# SmartSwitch_V1_3.net
KiCad netlist of a schematic drawn in EAGLE
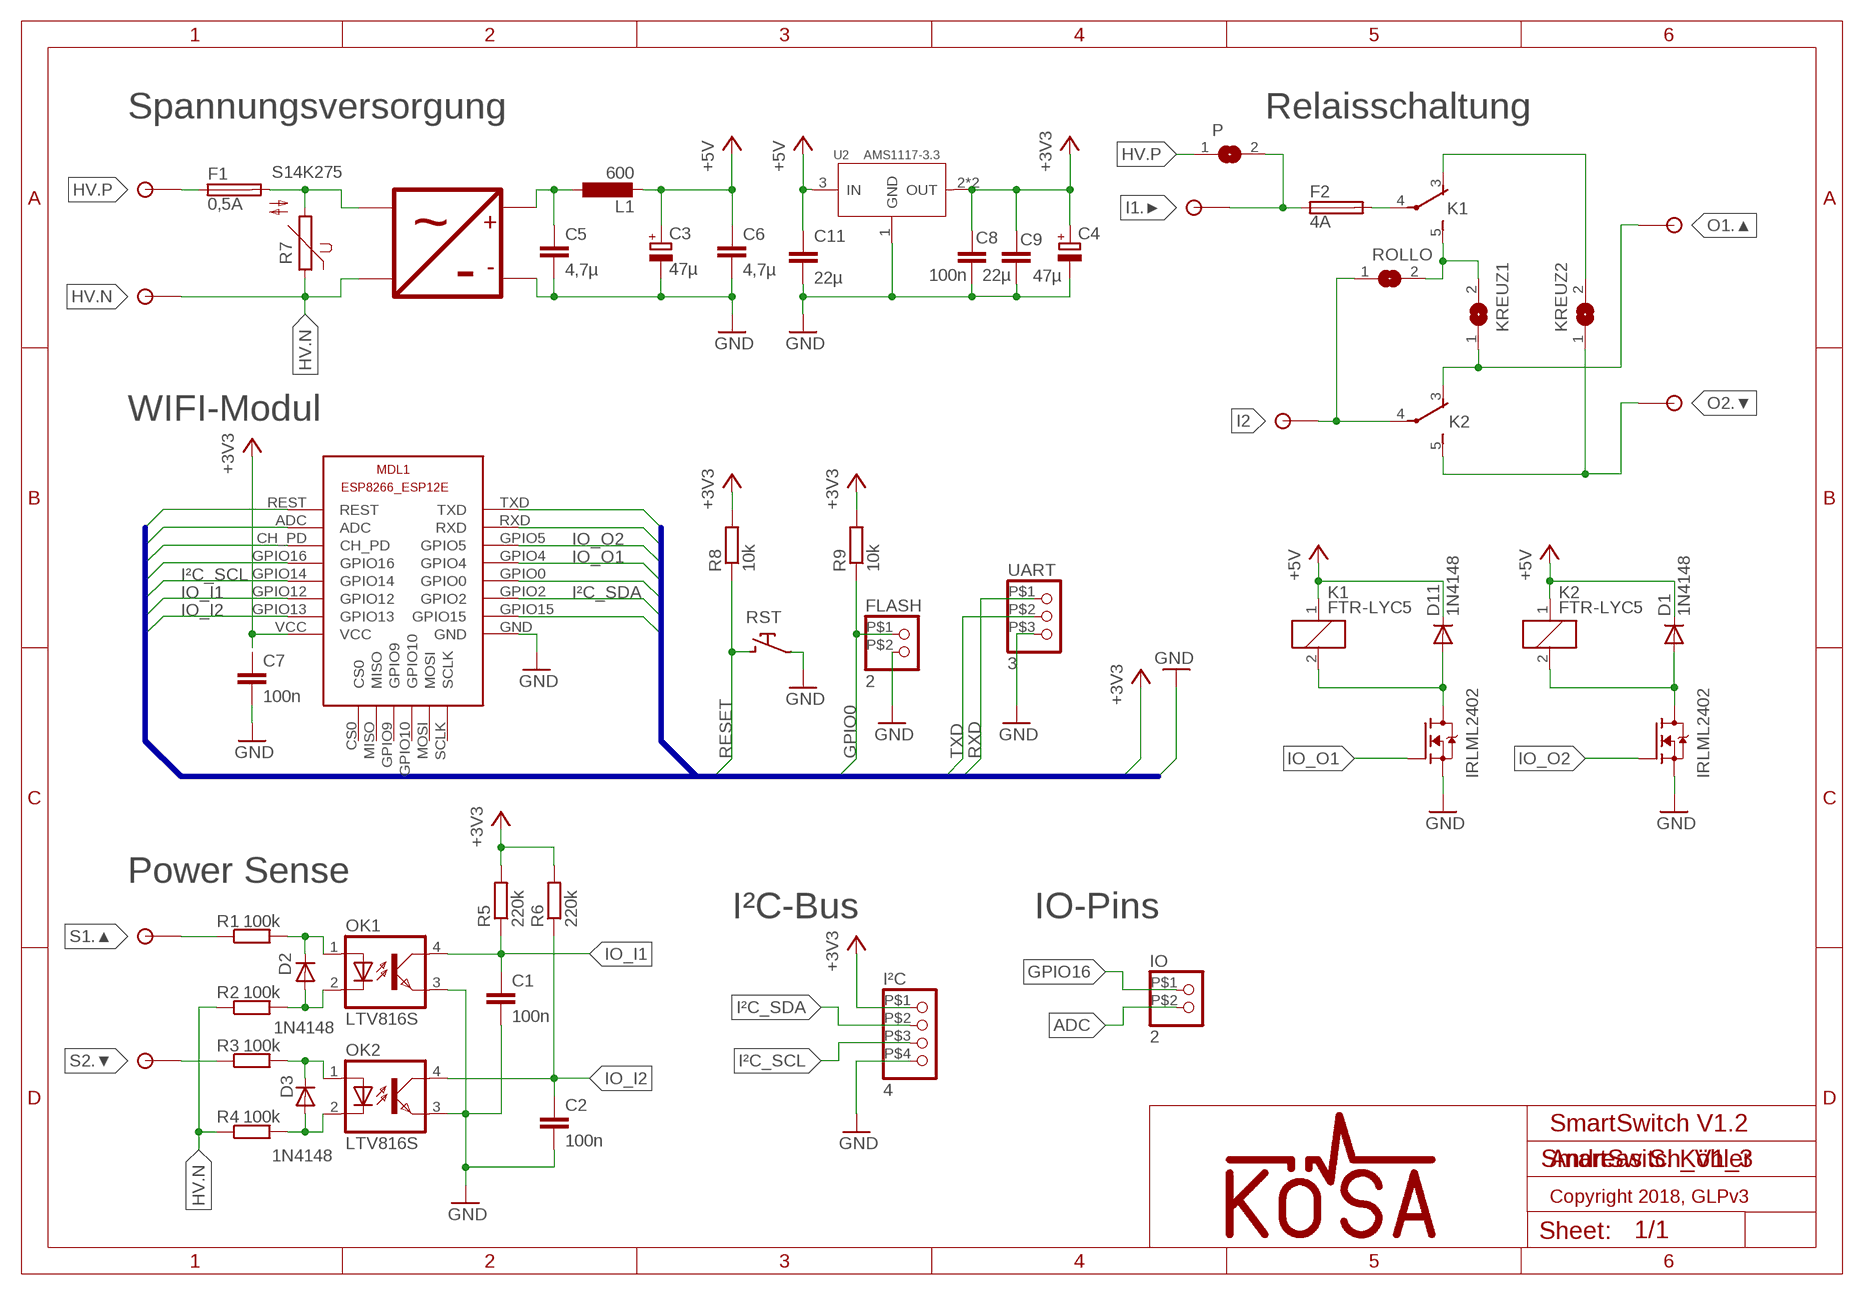
[diagram p0: schematic, sheet 1]

(export (version "E")
  (design (tool "Eeschema 10.0.6"))
  (components
    (comp (ref "C1")
      (value "100n")
      (footprint "eagle-import:C0805")
      (libsource (lib "eagle-import") (part "C-EUC0805"))
    )
    (comp (ref "C2")
      (value "100n")
      (footprint "eagle-import:C0805")
      (libsource (lib "eagle-import") (part "C-EUC0805"))
    )
    (comp (ref "C3")
      (value "47µ")
      (footprint "eagle-import:E2-5")
      (libsource (lib "eagle-import") (part "CPOL-EUE2-5"))
    )
    (comp (ref "C4")
      (value "47µ")
      (footprint "eagle-import:E2-5")
      (libsource (lib "eagle-import") (part "CPOL-EUE2-5"))
    )
    (comp (ref "C5")
      (value "4,7µ")
      (footprint "eagle-import:C0805")
      (libsource (lib "eagle-import") (part "C-EUC0805"))
    )
    (comp (ref "C6")
      (value "4,7µ")
      (footprint "eagle-import:C0805")
      (libsource (lib "eagle-import") (part "C-EUC0805"))
    )
    (comp (ref "C7")
      (value "100n")
      (footprint "eagle-import:C0805")
      (libsource (lib "eagle-import") (part "C-EUC0805"))
    )
    (comp (ref "C8")
      (value "100n")
      (footprint "eagle-import:C0805")
      (libsource (lib "eagle-import") (part "C-EUC0805"))
    )
    (comp (ref "C9")
      (value "22µ")
      (footprint "eagle-import:C0805")
      (libsource (lib "eagle-import") (part "C-EUC0805"))
    )
    (comp (ref "C11")
      (value "22µ")
      (footprint "eagle-import:C0805")
      (libsource (lib "eagle-import") (part "C-EUC0805"))
    )
    (comp (ref "D1")
      (value "1N4148")
      (footprint "eagle-import:SOD323-W")
      (libsource (lib "eagle-import") (part "DIODE-SOD323-W"))
    )
    (comp (ref "D2")
      (value "1N4148")
      (footprint "eagle-import:SOD323-W")
      (libsource (lib "eagle-import") (part "DIODE-SOD323-W"))
    )
    (comp (ref "D3")
      (value "1N4148")
      (footprint "eagle-import:SOD323-W")
      (libsource (lib "eagle-import") (part "DIODE-SOD323-W"))
    )
    (comp (ref "D11")
      (value "1N4148")
      (footprint "eagle-import:SOD323-W")
      (libsource (lib "eagle-import") (part "DIODE-SOD323-W"))
    )
    (comp (ref "F1")
      (value "0,5A")
      (footprint "eagle-import:SMD_FUSE_HOLDER")
      (libsource (lib "eagle-import") (part "SMD_FUSE_HOLDER"))
    )
    (comp (ref "F2")
      (value "4A")
      (footprint "eagle-import:SMD_FUSE_HOLDER")
      (libsource (lib "eagle-import") (part "SMD_FUSE_HOLDER"))
    )
    (comp (ref "FLASH")
      (value "2")
      (footprint "eagle-import:1X02_SMALL")
      (libsource (lib "eagle-import") (part "PINHD-1X2SMALL"))
    )
    (comp (ref "IO")
      (value "2")
      (footprint "eagle-import:1X02_SMALL")
      (libsource (lib "eagle-import") (part "PINHD-1X2SMALL"))
    )
    (comp (ref "I²C")
      (value "4")
      (footprint "eagle-import:1X04_SMALL")
      (libsource (lib "eagle-import") (part "PINHD-1X4SMALL"))
    )
    (comp (ref "K1")
      (value "FTR-LYC5")
      (footprint "eagle-import:FTR-LYC")
      (libsource (lib "eagle-import") (part "FTR-LYC5"))
    )
    (comp (ref "K2")
      (value "FTR-LYC5")
      (footprint "eagle-import:FTR-LYC")
      (libsource (lib "eagle-import") (part "FTR-LYC5"))
    )
    (comp (ref "KREUZ1")
      (value "SJW")
      (footprint "eagle-import:SJW")
      (libsource (lib "eagle-import") (part "SJW"))
    )
    (comp (ref "KREUZ2")
      (value "SJW")
      (footprint "eagle-import:SJW")
      (libsource (lib "eagle-import") (part "SJW"))
    )
    (comp (ref "L1")
      (value "600")
      (footprint "eagle-import:L3225P")
      (libsource (lib "eagle-import") (part "L-EUL3225P"))
    )
    (comp (ref "MDL1")
      (value "1")
      (footprint "eagle-import:ESP8266-ESP12E")
      (libsource (lib "eagle-import") (part "ESP8266-12EESP8266-ESP12E"))
    )
    (comp (ref "OK1")
      (value "LTV816S")
      (footprint "eagle-import:SMD4")
      (libsource (lib "eagle-import") (part "LTV816S"))
    )
    (comp (ref "OK2")
      (value "LTV816S")
      (footprint "eagle-import:SMD4")
      (libsource (lib "eagle-import") (part "LTV816S"))
    )
    (comp (ref "P")
      (value "SJW")
      (footprint "eagle-import:SJW")
      (libsource (lib "eagle-import") (part "SJW"))
    )
    (comp (ref "R1")
      (value "100k")
      (footprint "eagle-import:R1206")
      (libsource (lib "eagle-import") (part "R-EU_R1206"))
    )
    (comp (ref "R2")
      (value "100k")
      (footprint "eagle-import:R1206")
      (libsource (lib "eagle-import") (part "R-EU_R1206"))
    )
    (comp (ref "R3")
      (value "100k")
      (footprint "eagle-import:R1206")
      (libsource (lib "eagle-import") (part "R-EU_R1206"))
    )
    (comp (ref "R4")
      (value "100k")
      (footprint "eagle-import:R1206")
      (libsource (lib "eagle-import") (part "R-EU_R1206"))
    )
    (comp (ref "R5")
      (value "220k")
      (footprint "eagle-import:R1206")
      (libsource (lib "eagle-import") (part "R-EU_R1206"))
    )
    (comp (ref "R6")
      (value "220k")
      (footprint "eagle-import:R1206")
      (libsource (lib "eagle-import") (part "R-EU_R1206"))
    )
    (comp (ref "R7")
      (value "S14K275")
      (footprint "eagle-import:S14K275_")
      (libsource (lib "eagle-import") (part "S14K275GESPIEGELT"))
    )
    (comp (ref "R8")
      (value "10k")
      (footprint "eagle-import:R1206")
      (libsource (lib "eagle-import") (part "R-EU_R1206"))
    )
    (comp (ref "R9")
      (value "10k")
      (footprint "eagle-import:R1206")
      (libsource (lib "eagle-import") (part "R-EU_R1206"))
    )
    (comp (ref "ROLLO")
      (value "SJW")
      (footprint "eagle-import:SJW")
      (libsource (lib "eagle-import") (part "SJW"))
    )
    (comp (ref "RST")
      (value "SMD-TASTER_REICHELT_KMR_231_G_LFS")
      (footprint "eagle-import:SMD-TASTER_REICHELT_KMR_231_G_LFS")
      (libsource (lib "eagle-import") (part "SMD-TASTER_REICHELT_KMR_231_G_LFS"))
    )
    (comp (ref "U$1")
      (value "HLK-PM01")
      (footprint "eagle-import:HLK-PM01")
      (libsource (lib "eagle-import") (part "HLK-PM01"))
    )
    (comp (ref "U$2")
      (value "RND_205-00276")
      (footprint "eagle-import:RND205-00276")
      (libsource (lib "eagle-import") (part "RND_205-00276"))
    )
    (comp (ref "U$3")
      (value "RND_205-00276")
      (footprint "eagle-import:RND205-00276")
      (libsource (lib "eagle-import") (part "RND_205-00276"))
    )
    (comp (ref "U$4")
      (value "RND_205-00276")
      (footprint "eagle-import:RND205-00276")
      (libsource (lib "eagle-import") (part "RND_205-00276"))
    )
    (comp (ref "U$5")
      (value "RND_205-00276")
      (footprint "eagle-import:RND205-00276")
      (libsource (lib "eagle-import") (part "RND_205-00276"))
    )
    (comp (ref "U$7")
      (value "IRLML2402")
      (footprint "eagle-import:SOT23")
      (libsource (lib "eagle-import") (part "IRLML2502"))
    )
    (comp (ref "U$8")
      (value "IRLML2402")
      (footprint "eagle-import:SOT23")
      (libsource (lib "eagle-import") (part "IRLML2502"))
    )
    (comp (ref "U2")
      (value "AMS1117-3.3")
      (footprint "eagle-import:SOT-223")
      (fields (field (name "MPN") "CJT1117-3.3"))
      (libsource (lib "eagle-import") (part "PMIC-CJT1117-3.3(SOT223)"))
    )
    (comp (ref "UART")
      (value "3")
      (footprint "eagle-import:1X03_SMALL")
      (libsource (lib "eagle-import") (part "PINHD-1X3SMALL"))
    )
  )
  (nets
    (net (code "1") (name "+3V3") (class "Default")
      (node (ref "C4") (pin "+") (pinfunction "+_+") (pintype "passive"))
      (node (ref "C7") (pin "1") (pinfunction "1_1") (pintype "passive"))
      (node (ref "C8") (pin "1") (pinfunction "1_1") (pintype "passive"))
      (node (ref "C9") (pin "1") (pinfunction "1_1") (pintype "passive"))
      (node (ref "I²C") (pin "P$1") (pinfunction "1_P$1") (pintype "passive"))
      (node (ref "MDL1") (pin "CH_PD") (pinfunction "CH_PD_CH_PD") (pintype "bidirectional"))
      (node (ref "MDL1") (pin "VCC") (pinfunction "VCC_VCC") (pintype "bidirectional"))
      (node (ref "R5") (pin "2") (pinfunction "2_2") (pintype "passive"))
      (node (ref "R6") (pin "2") (pinfunction "2_2") (pintype "passive"))
      (node (ref "R8") (pin "2") (pinfunction "2_2") (pintype "passive"))
      (node (ref "R9") (pin "2") (pinfunction "2_2") (pintype "passive"))
      (node (ref "U2") (pin "2") (pinfunction "OUT_2") (pintype "bidirectional"))
      (node (ref "U2") (pin "TER") (pinfunction "OUT_TER") (pintype "bidirectional"))
    )
    (net (code "2") (name "+5V") (class "Default")
      (node (ref "C11") (pin "1") (pinfunction "1_1") (pintype "passive"))
      (node (ref "C3") (pin "+") (pinfunction "+_+") (pintype "passive"))
      (node (ref "C6") (pin "1") (pinfunction "1_1") (pintype "passive"))
      (node (ref "D1") (pin "C") (pinfunction "C_C") (pintype "passive"))
      (node (ref "D11") (pin "C") (pinfunction "C_C") (pintype "passive"))
      (node (ref "K1") (pin "1") (pinfunction "1_1") (pintype "passive"))
      (node (ref "K2") (pin "1") (pinfunction "1_1") (pintype "passive"))
      (node (ref "L1") (pin "2") (pinfunction "2_2") (pintype "passive"))
      (node (ref "U2") (pin "3") (pinfunction "IN_3") (pintype "bidirectional"))
    )
    (net (code "3") (name "/GPIO0") (class "Default")
      (node (ref "FLASH") (pin "P$1") (pinfunction "1_P$1") (pintype "passive"))
      (node (ref "MDL1") (pin "GPIO0") (pinfunction "GPIO0_GPIO0") (pintype "bidirectional"))
      (node (ref "R9") (pin "1") (pinfunction "1_1") (pintype "passive"))
    )
    (net (code "4") (name "/RESET") (class "Default")
      (node (ref "MDL1") (pin "REST") (pinfunction "REST_REST") (pintype "bidirectional"))
      (node (ref "R8") (pin "1") (pinfunction "1_1") (pintype "passive"))
      (node (ref "RST") (pin "2_1") (pinfunction "B_2_1") (pintype "bidirectional"))
      (node (ref "RST") (pin "2_2") (pinfunction "B_2_2") (pintype "bidirectional"))
    )
    (net (code "5") (name "/RXD") (class "Default")
      (node (ref "MDL1") (pin "RXD") (pinfunction "RXD_RXD") (pintype "bidirectional"))
      (node (ref "UART") (pin "P$1") (pinfunction "1_P$1") (pintype "passive"))
    )
    (net (code "6") (name "/TXD") (class "Default")
      (node (ref "MDL1") (pin "TXD") (pinfunction "TXD_TXD") (pintype "bidirectional"))
      (node (ref "UART") (pin "P$2") (pinfunction "2_P$2") (pintype "passive"))
    )
    (net (code "7") (name "ADC") (class "Default")
      (node (ref "IO") (pin "P$2") (pinfunction "2_P$2") (pintype "passive"))
      (node (ref "MDL1") (pin "ADC") (pinfunction "ADC_ADC") (pintype "bidirectional"))
    )
    (net (code "8") (name "GND") (class "Default")
      (node (ref "C1") (pin "2") (pinfunction "2_2") (pintype "passive"))
      (node (ref "C11") (pin "2") (pinfunction "2_2") (pintype "passive"))
      (node (ref "C2") (pin "2") (pinfunction "2_2") (pintype "passive"))
      (node (ref "C3") (pin "-") (pinfunction "-_-") (pintype "passive"))
      (node (ref "C4") (pin "-") (pinfunction "-_-") (pintype "passive"))
      (node (ref "C5") (pin "2") (pinfunction "2_2") (pintype "passive"))
      (node (ref "C6") (pin "2") (pinfunction "2_2") (pintype "passive"))
      (node (ref "C7") (pin "2") (pinfunction "2_2") (pintype "passive"))
      (node (ref "C8") (pin "2") (pinfunction "2_2") (pintype "passive"))
      (node (ref "C9") (pin "2") (pinfunction "2_2") (pintype "passive"))
      (node (ref "FLASH") (pin "P$2") (pinfunction "2_P$2") (pintype "passive"))
      (node (ref "I²C") (pin "P$4") (pinfunction "4_P$4") (pintype "passive"))
      (node (ref "MDL1") (pin "GND") (pinfunction "GND_GND") (pintype "bidirectional"))
      (node (ref "MDL1") (pin "GPIO15") (pinfunction "GPIO15_GPIO15") (pintype "bidirectional"))
      (node (ref "OK1") (pin "3") (pinfunction "EMIT_3") (pintype "passive"))
      (node (ref "OK2") (pin "3") (pinfunction "EMIT_3") (pintype "passive"))
      (node (ref "RST") (pin "1_1") (pinfunction "A_1_1") (pintype "bidirectional"))
      (node (ref "RST") (pin "1_2") (pinfunction "A_1_2") (pintype "bidirectional"))
      (node (ref "U$1") (pin "DC-") (pinfunction "DC-_DC-") (pintype "power_in"))
      (node (ref "U$7") (pin "2") (pinfunction "S_2") (pintype "passive"))
      (node (ref "U$8") (pin "2") (pinfunction "S_2") (pintype "passive"))
      (node (ref "U2") (pin "1") (pinfunction "GND_1") (pintype "bidirectional"))
      (node (ref "UART") (pin "P$3") (pinfunction "3_P$3") (pintype "passive"))
    )
    (net (code "9") (name "GPIO16") (class "Default")
      (node (ref "IO") (pin "P$1") (pinfunction "1_P$1") (pintype "passive"))
      (node (ref "MDL1") (pin "GPIO16") (pinfunction "GPIO16_GPIO16") (pintype "bidirectional"))
    )
    (net (code "10") (name "HV.N") (class "Default")
      (node (ref "R2") (pin "1") (pinfunction "1_1") (pintype "passive"))
      (node (ref "R4") (pin "1") (pinfunction "1_1") (pintype "passive"))
      (node (ref "R7") (pin "1") (pinfunction "1_1") (pintype "passive"))
      (node (ref "U$1") (pin "AC2") (pinfunction "AC2_AC2") (pintype "power_in"))
      (node (ref "U$2") (pin "P$2") (pinfunction "P$1_P$2") (pintype "bidirectional"))
    )
    (net (code "11") (name "HV.P") (class "Default")
      (node (ref "F1") (pin "P$1") (pinfunction "1_P$1") (pintype "passive"))
      (node (ref "P") (pin "1") (pinfunction "1_1") (pintype "passive"))
      (node (ref "U$2") (pin "P$1") (pinfunction "P$1_P$1") (pintype "bidirectional"))
    )
    (net (code "12") (name "I1.►") (class "Default")
      (node (ref "F2") (pin "P$1") (pinfunction "1_P$1") (pintype "passive"))
      (node (ref "P") (pin "2") (pinfunction "2_2") (pintype "passive"))
      (node (ref "U$4") (pin "P$1") (pinfunction "P$1_P$1") (pintype "bidirectional"))
    )
    (net (code "13") (name "I2") (class "Default")
      (node (ref "K2") (pin "4") (pinfunction "P_4") (pintype "passive"))
      (node (ref "ROLLO") (pin "1") (pinfunction "1_1") (pintype "passive"))
      (node (ref "U$3") (pin "P$1") (pinfunction "P$1_P$1") (pintype "bidirectional"))
    )
    (net (code "14") (name "IO_I1") (class "Default")
      (node (ref "C1") (pin "1") (pinfunction "1_1") (pintype "passive"))
      (node (ref "MDL1") (pin "GPIO12") (pinfunction "GPIO12_GPIO12") (pintype "bidirectional"))
      (node (ref "OK1") (pin "4") (pinfunction "COL_4") (pintype "passive"))
      (node (ref "R5") (pin "1") (pinfunction "1_1") (pintype "passive"))
    )
    (net (code "15") (name "IO_I2") (class "Default")
      (node (ref "C2") (pin "1") (pinfunction "1_1") (pintype "passive"))
      (node (ref "MDL1") (pin "GPIO13") (pinfunction "GPIO13_GPIO13") (pintype "bidirectional"))
      (node (ref "OK2") (pin "4") (pinfunction "COL_4") (pintype "passive"))
      (node (ref "R6") (pin "1") (pinfunction "1_1") (pintype "passive"))
    )
    (net (code "16") (name "IO_O1") (class "Default")
      (node (ref "MDL1") (pin "GPIO4") (pinfunction "GPIO4_GPIO4") (pintype "bidirectional"))
      (node (ref "U$7") (pin "1") (pinfunction "G_1") (pintype "passive"))
    )
    (net (code "17") (name "IO_O2") (class "Default")
      (node (ref "MDL1") (pin "GPIO5") (pinfunction "GPIO5_GPIO5") (pintype "bidirectional"))
      (node (ref "U$8") (pin "1") (pinfunction "G_1") (pintype "passive"))
    )
    (net (code "18") (name "I²C_SCL") (class "Default")
      (node (ref "I²C") (pin "P$3") (pinfunction "3_P$3") (pintype "passive"))
      (node (ref "MDL1") (pin "GPIO14") (pinfunction "GPIO14_GPIO14") (pintype "bidirectional"))
    )
    (net (code "19") (name "I²C_SDA") (class "Default")
      (node (ref "I²C") (pin "P$2") (pinfunction "2_P$2") (pintype "passive"))
      (node (ref "MDL1") (pin "GPIO2") (pinfunction "GPIO2_GPIO2") (pintype "bidirectional"))
    )
    (net (code "20") (name "Net-(C5-Pad1)") (class "Default")
      (node (ref "C5") (pin "1") (pinfunction "1_1") (pintype "passive"))
      (node (ref "L1") (pin "1") (pinfunction "1_1") (pintype "passive"))
      (node (ref "U$1") (pin "DC+") (pinfunction "DC+_DC+") (pintype "power_in"))
    )
    (net (code "21") (name "Net-(F1-2)") (class "Default")
      (node (ref "F1") (pin "P$2") (pinfunction "2_P$2") (pintype "passive"))
      (node (ref "R7") (pin "2") (pinfunction "2_2") (pintype "passive"))
      (node (ref "U$1") (pin "AC1") (pinfunction "AC1_AC1") (pintype "power_in"))
    )
    (net (code "22") (name "Net-(F2-2)") (class "Default")
      (node (ref "F2") (pin "P$2") (pinfunction "2_P$2") (pintype "passive"))
      (node (ref "K1") (pin "4") (pinfunction "P_4") (pintype "passive"))
    )
    (net (code "23") (name "Net-(K1A-O)") (class "Default")
      (node (ref "K1") (pin "3") (pinfunction "O_3") (pintype "passive"))
      (node (ref "KREUZ2") (pin "2") (pinfunction "2_2") (pintype "passive"))
    )
    (net (code "24") (name "Net-(K1A-S)") (class "Default")
      (node (ref "K1") (pin "5") (pinfunction "S_5") (pintype "passive"))
      (node (ref "KREUZ1") (pin "2") (pinfunction "2_2") (pintype "passive"))
      (node (ref "ROLLO") (pin "2") (pinfunction "2_2") (pintype "passive"))
    )
    (net (code "25") (name "Net-(OK1-A)") (class "Default")
      (node (ref "D2") (pin "C") (pinfunction "C_C") (pintype "passive"))
      (node (ref "OK1") (pin "1") (pinfunction "A_1") (pintype "passive"))
      (node (ref "R1") (pin "2") (pinfunction "2_2") (pintype "passive"))
    )
    (net (code "26") (name "Net-(OK1-C)") (class "Default")
      (node (ref "D2") (pin "A") (pinfunction "A_A") (pintype "passive"))
      (node (ref "OK1") (pin "2") (pinfunction "C_2") (pintype "passive"))
      (node (ref "R2") (pin "2") (pinfunction "2_2") (pintype "passive"))
    )
    (net (code "27") (name "Net-(OK2-A)") (class "Default")
      (node (ref "D3") (pin "C") (pinfunction "C_C") (pintype "passive"))
      (node (ref "OK2") (pin "1") (pinfunction "A_1") (pintype "passive"))
      (node (ref "R3") (pin "2") (pinfunction "2_2") (pintype "passive"))
    )
    (net (code "28") (name "Net-(OK2-C)") (class "Default")
      (node (ref "D3") (pin "A") (pinfunction "A_A") (pintype "passive"))
      (node (ref "OK2") (pin "2") (pinfunction "C_2") (pintype "passive"))
      (node (ref "R4") (pin "2") (pinfunction "2_2") (pintype "passive"))
    )
    (net (code "29") (name "Net-(U$7-D)") (class "Default")
      (node (ref "D11") (pin "A") (pinfunction "A_A") (pintype "passive"))
      (node (ref "K1") (pin "2") (pinfunction "2_2") (pintype "passive"))
      (node (ref "U$7") (pin "3") (pinfunction "D_3") (pintype "passive"))
    )
    (net (code "30") (name "Net-(U$8-D)") (class "Default")
      (node (ref "D1") (pin "A") (pinfunction "A_A") (pintype "passive"))
      (node (ref "K2") (pin "2") (pinfunction "2_2") (pintype "passive"))
      (node (ref "U$8") (pin "3") (pinfunction "D_3") (pintype "passive"))
    )
    (net (code "31") (name "O1.▲") (class "Default")
      (node (ref "K2") (pin "3") (pinfunction "O_3") (pintype "passive"))
      (node (ref "KREUZ1") (pin "1") (pinfunction "1_1") (pintype "passive"))
      (node (ref "U$3") (pin "P$2") (pinfunction "P$1_P$2") (pintype "bidirectional"))
    )
    (net (code "32") (name "O2.▼") (class "Default")
      (node (ref "K2") (pin "5") (pinfunction "S_5") (pintype "passive"))
      (node (ref "KREUZ2") (pin "1") (pinfunction "1_1") (pintype "passive"))
      (node (ref "U$4") (pin "P$2") (pinfunction "P$1_P$2") (pintype "bidirectional"))
    )
    (net (code "33") (name "S1.▲") (class "Default")
      (node (ref "R1") (pin "1") (pinfunction "1_1") (pintype "passive"))
      (node (ref "U$5") (pin "P$2") (pinfunction "P$1_P$2") (pintype "bidirectional"))
    )
    (net (code "34") (name "S2.▼") (class "Default")
      (node (ref "R3") (pin "1") (pinfunction "1_1") (pintype "passive"))
      (node (ref "U$5") (pin "P$1") (pinfunction "P$1_P$1") (pintype "bidirectional"))
    )
    (net (code "35") (name "unconnected-(MDL1-PadCS0)") (class "Default")
      (node (ref "MDL1") (pin "CS0") (pinfunction "CS0_CS0") (pintype "bidirectional"))
    )
    (net (code "36") (name "unconnected-(MDL1-PadGPIO9)") (class "Default")
      (node (ref "MDL1") (pin "GPIO9") (pinfunction "GPIO9_GPIO9") (pintype "bidirectional"))
    )
    (net (code "37") (name "unconnected-(MDL1-PadGPIO10)") (class "Default")
      (node (ref "MDL1") (pin "GPIO10") (pinfunction "GPIO10_GPIO10") (pintype "bidirectional"))
    )
    (net (code "38") (name "unconnected-(MDL1-PadMISO)") (class "Default")
      (node (ref "MDL1") (pin "MISO") (pinfunction "MISO_MISO") (pintype "bidirectional"))
    )
    (net (code "39") (name "unconnected-(MDL1-PadMOSI)") (class "Default")
      (node (ref "MDL1") (pin "MOSI") (pinfunction "MOSI_MOSI") (pintype "bidirectional"))
    )
    (net (code "40") (name "unconnected-(MDL1-PadSCLK)") (class "Default")
      (node (ref "MDL1") (pin "SCLK") (pinfunction "SCLK_SCLK") (pintype "bidirectional"))
    )
  )
)
